# 29-USB_2_0_INTERFACE.net
KiCad netlist of a schematic drawn in Altium Designer
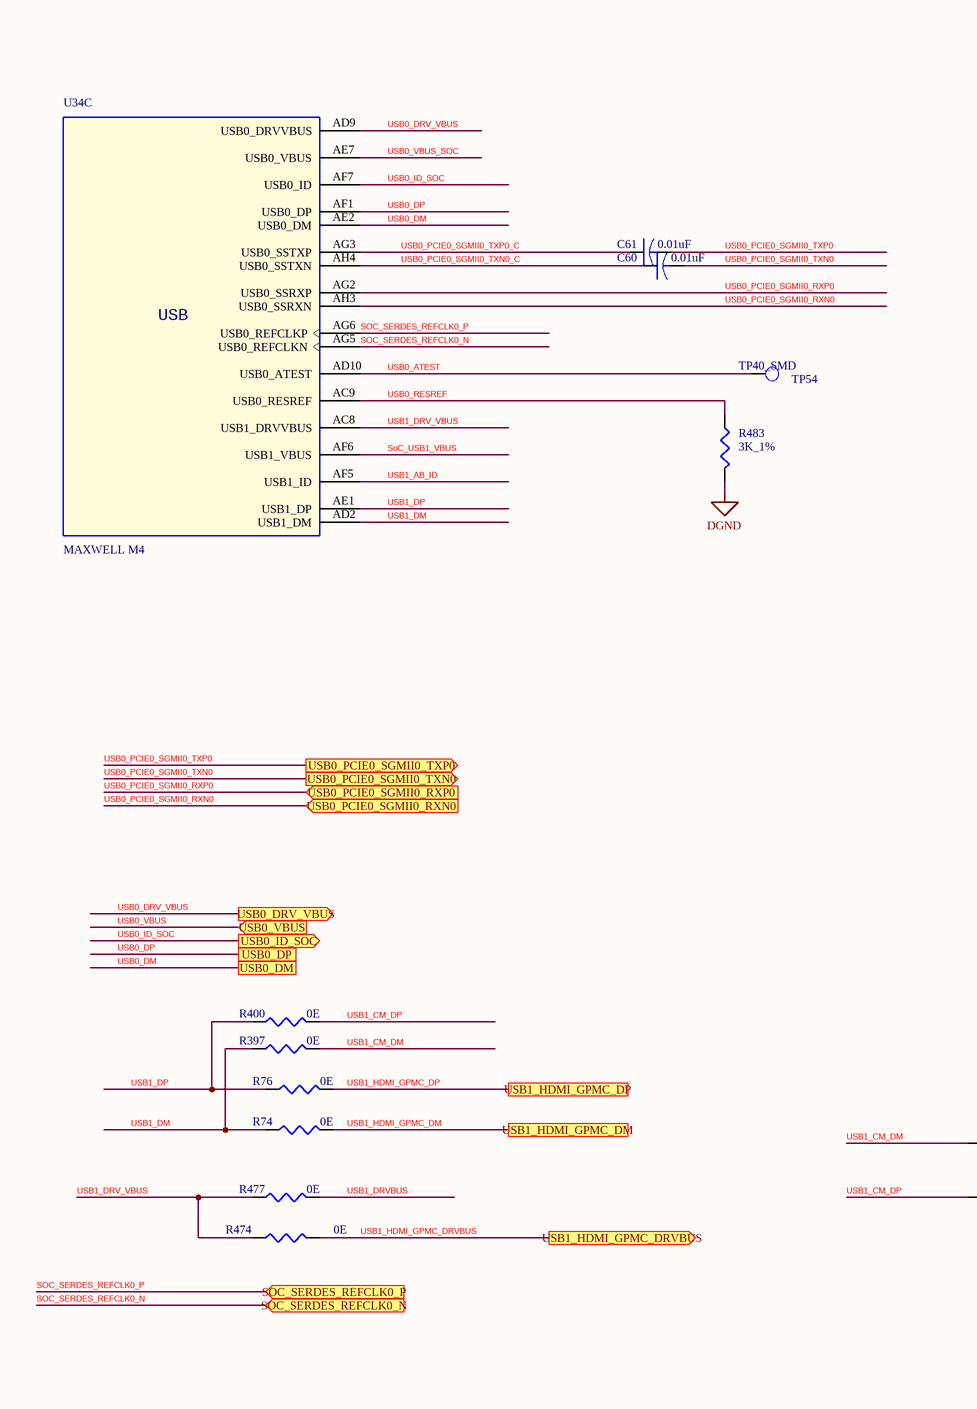
[diagram p0: 29-USB 2.0 INTERFACE.SchDoc, left]
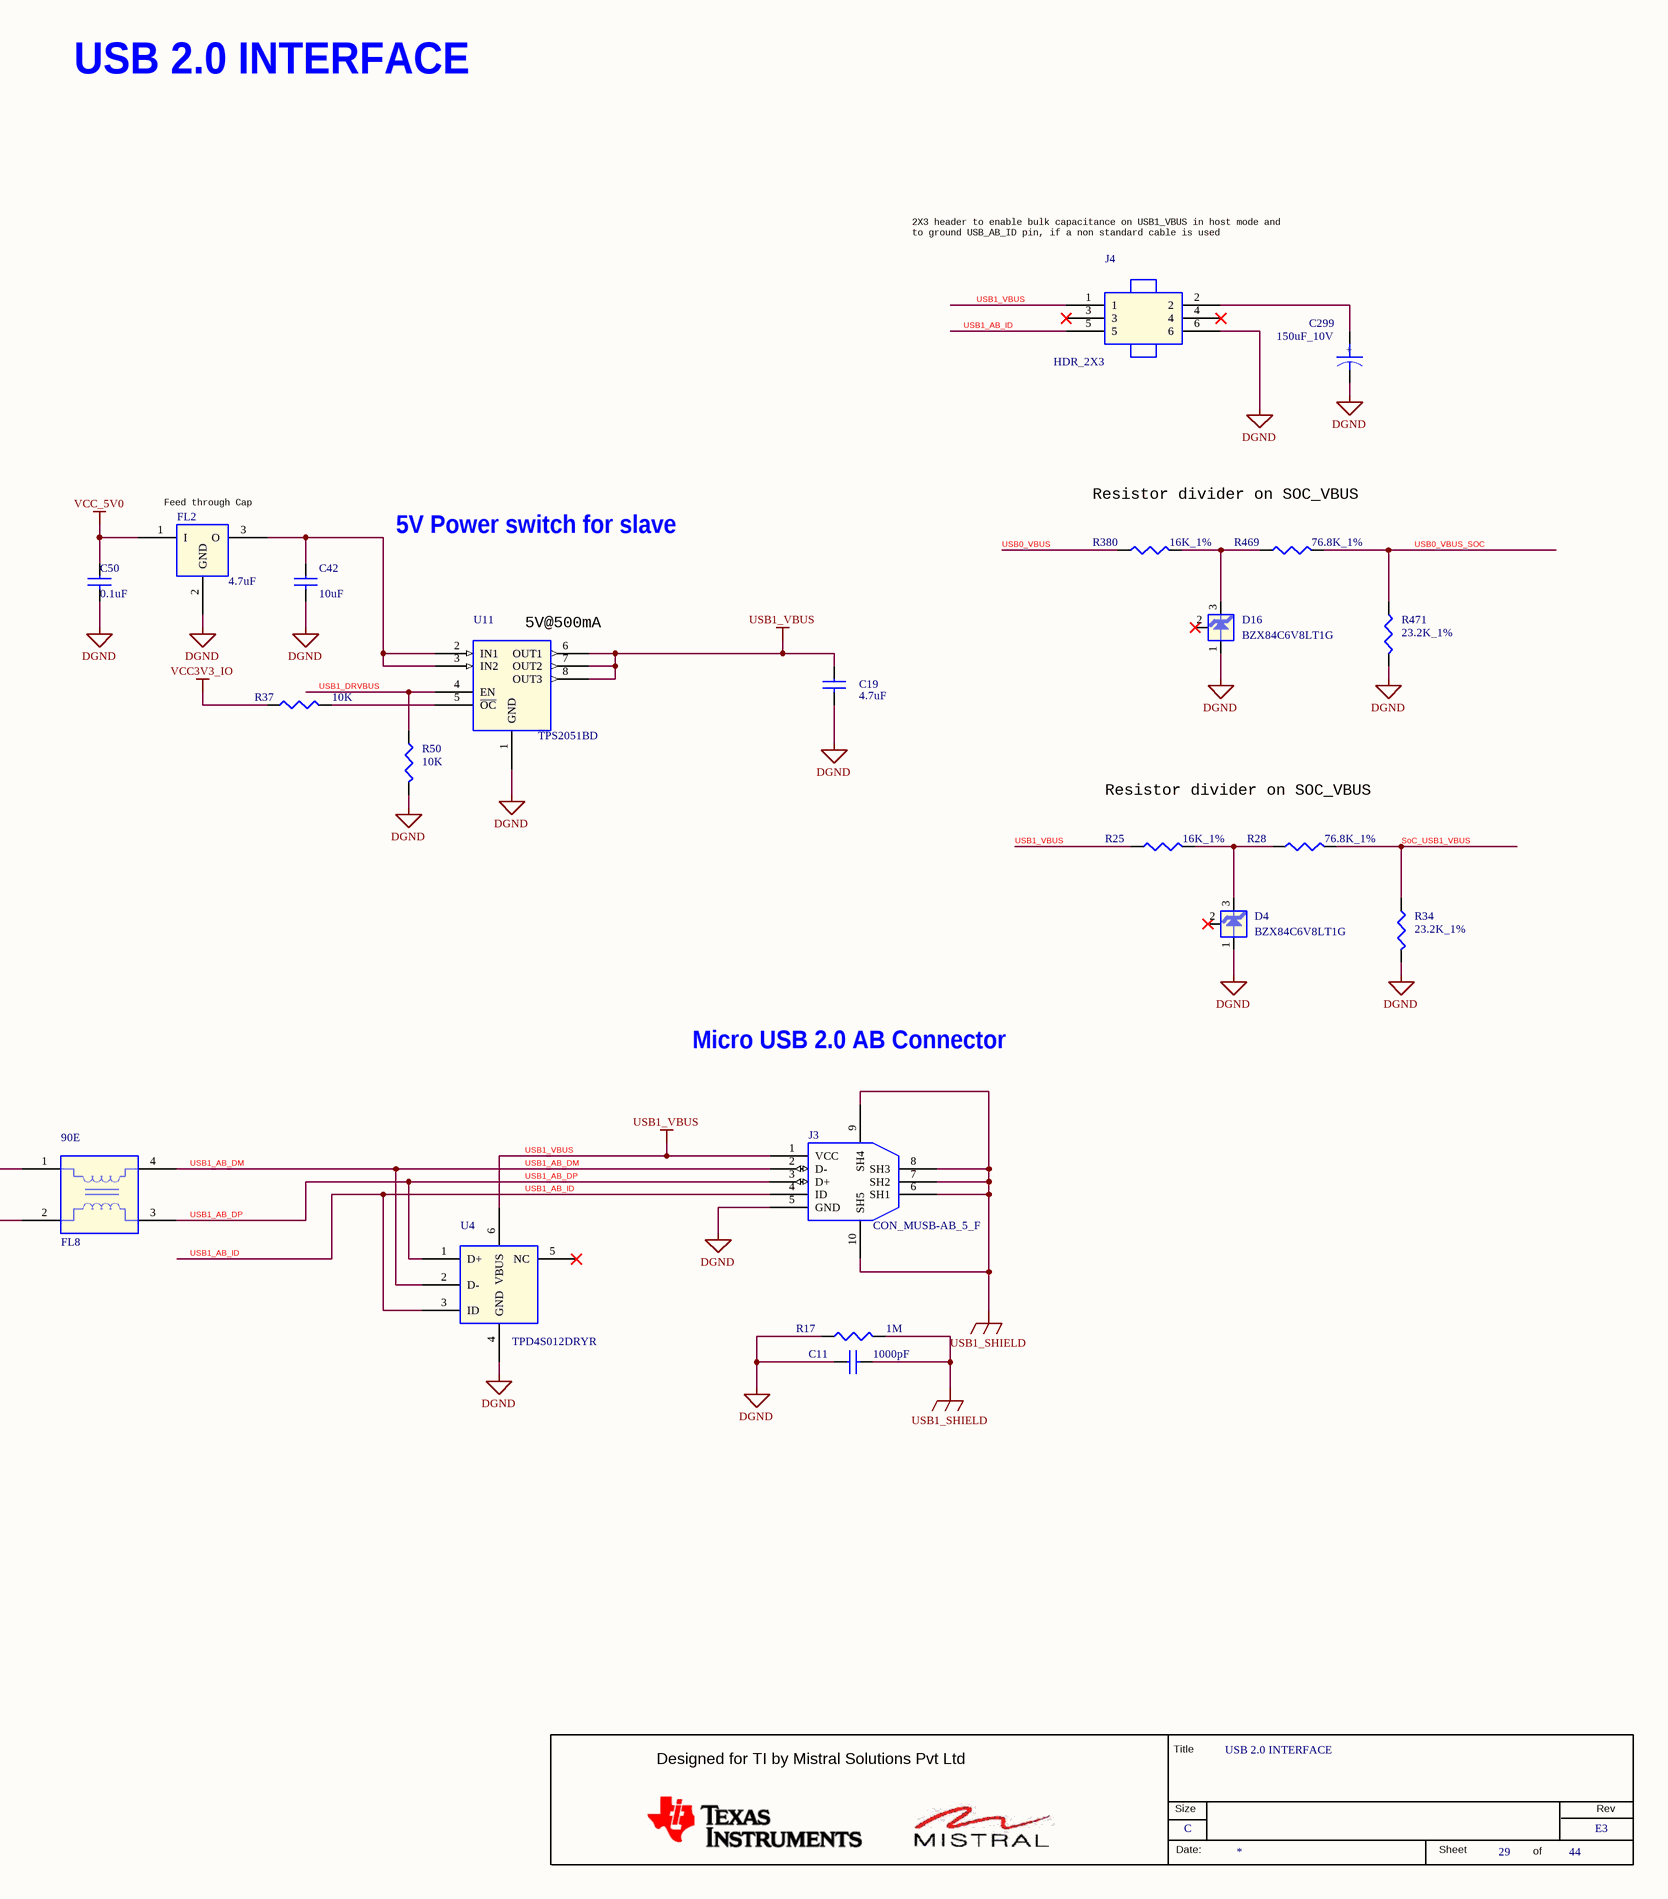
[diagram p1: 29-USB 2.0 INTERFACE.SchDoc, right]

(export (version "E")
  (design (tool "Eeschema 10.0.6"))
  (components
    (comp (ref "C11")
      (value "1000pF")
      (footprint "CAP1206")
      (description "CAP CERAMIC 1000pF 2KV 10% X7R 1206")
      (fields (field (name "DISTRIBUTOR_PART_NUMBER") "478-2956-1-ND") (field (name "VOLTAGE") "2KV"))
      (libsource (lib "*") (part "CAP_Dup5"))
    )
    (comp (ref "C19")
      (value "4.7uF")
      (footprint "CAP0402_0-75")
      (description "CAP CERAMIC 4.7uF 10V 20% X5R 0402")
      (fields
        (field (name "MISTRAL PART NO") "120012060002-R")
        (field (name "MFR_PART_NUMBER") "0402ZD475MAT2A")
      )
      (libsource (lib "*") (part "CAP_Dup5"))
    )
    (comp (ref "C42")
      (value "10uF")
      (footprint "CAP0603_1")
      (description "CAP CERAMIC 10uF 10V 10% X5R 0603")
      (fields (field (name "DISTRIBUTOR_PART_NUMBER") "478-10766-1-ND") (field (name "VOLTAGE") "10V"))
      (libsource (lib "*") (part "CAP_Dup5"))
    )
    (comp (ref "C50")
      (value "0.1uF")
      (footprint "CAP0201_0-5")
      (description "CAP CERAMIC 0.1uF 16V 10% X5R 0201")
      (fields
        (field (name "MISTRAL PART NO") "120009030072-R")
        (field (name "MFR_PART_NUMBER") "GRM033R61C104KE84J")
      )
      (libsource (lib "*") (part "CAP_Dup5"))
    )
    (comp (ref "C60")
      (value "0.01uF")
      (footprint "CAP0402_0-75")
      (description "CAP CERAMIC 0.01uF 10V 10% X7R 0402")
      (fields
        (field (name "MISTRAL PART NO") "120009030017-R")
        (field (name "MFR_PART_NUMBER") "0402ZC103KAT2A")
      )
      (libsource (lib "*") (part "CAP"))
    )
    (comp (ref "C61")
      (value "0.01uF")
      (footprint "CAP0402_0-75")
      (description "CAP CERAMIC 0.01uF 10V 10% X7R 0402")
      (fields (field (name "DISTRIBUTOR_PART_NUMBER") "478-7890-1-ND") (field (name "VOLTAGE") "10V"))
      (libsource (lib "*") (part "CAP"))
    )
    (comp (ref "C299")
      (value "150uF_10V")
      (footprint "CAPT7343D_3-25")
      (description "CAP TANTALUM 150uF 10V 10% ESR 0.9E D7373")
      (fields (field (name "DISTRIBUTOR_PART_NUMBER") "478-11241-1-ND") (field (name "VOLTAGE") "10V"))
      (libsource (lib "*") (part "CAP_POL"))
    )
    (comp (ref "D4")
      (value "BZX84C6V8LT1G")
      (footprint "SOT23-123_1-2")
      (description "DIODE ZENER 250mW 6.8V SOT23-123")
      (fields (field (name "MISTRAL PART NO") "130017100002-R") (field (name "TOLERANCE") "NA"))
      (libsource (lib "*") (part "DIODE_ZENER_SOT23_13"))
    )
    (comp (ref "D16")
      (value "BZX84C6V8LT1G")
      (footprint "SOT23-123_1-2")
      (description "DIODE ZENER 250mW 6.8V SOT23-123")
      (fields (field (name "MISTRAL PART NO") "130017100002-R") (field (name "TOLERANCE") "NA"))
      (libsource (lib "*") (part "DIODE_ZENER_SOT23_13"))
    )
    (comp (ref "FL2")
      (value "4.7uF")
      (footprint "EMIFIL_NFM21P_0805_1")
      (description "PASSIVE FILTER EMI 4.7uF 0805-3")
      (fields (field (name "DISTRIBUTOR_PART_NUMBER") "NA") (field (name "MFR_PART_NUMBER") "NFM21PC475B1A3"))
      (libsource (lib "*") (part "EMI_FILTER"))
    )
    (comp (ref "FL8")
      (value "90E")
      (footprint "IND4_ACM2012_90X50_SMD_1-3")
      (description "PASSIVE FILTER COMMON MODE 90E 400mA SMD")
      (fields
        (field (name "DISTRIBUTOR_PART_NUMBER") "445-2207-1-ND")
        (field (name "MFR_PART_NUMBER") "ACM2012-900-2P-T002")
      )
      (libsource (lib "*") (part "EMIFILTER_ACM"))
    )
    (comp (ref "J3")
      (value "CON_MUSB-AB_5_F")
      (footprint "CON_USBAB5_475900001_S_R_S_3-1")
      (description "CON MICRO USB-AB TYPE 5POS FEMALE RT SMD")
      (fields (field (name "DISTRIBUTOR_PART_NUMBER") "WM17144CT-ND") (field (name "VOLTAGE") "NA"))
      (libsource (lib "*") (part "CON_USB_MINI-AB_10"))
    )
    (comp (ref "J4")
      (value "HDR_2X3")
      (footprint "TMDX654GPEVM_BRD:HDR_2X3_TSW-103-07-D_S_T_8-4")
      (description "CON HDR 2X3 2.54MM PITCH ST TH")
      (fields
        (field (name "MISTRAL PART NO") "150018010019-R")
        (field (name "MFR_PART_NUMBER") "TSW-103-07-T-D")
      )
      (libsource (lib "*") (part "HEADER_3X2"))
    )
    (comp (ref "R17")
      (value "1M")
      (footprint "RES0603_0-75")
      (description "RES 1M 1/10W 5% 0603")
      (fields (field (name "DISTRIBUTOR_PART_NUMBER") "P1.0MGCT-ND") (field (name "VOLTAGE") "NA"))
      (libsource (lib "*") (part "RESISTOR_Dup5"))
    )
    (comp (ref "R25")
      (value "16K_1%")
      (footprint "RES0402")
      (description "RES 16K 1/16W 1% 0402")
      (fields
        (field (name "MISTRAL PART NO") "110011030003-R")
        (field (name "MFR_PART_NUMBER") "MCR01MRTF1602")
      )
      (libsource (lib "*") (part "RESISTOR_Dup5"))
    )
    (comp (ref "R28")
      (value "76.8K_1%")
      (footprint "RES0402")
      (description "RES 76.8K 1/16W 1% 0402")
      (fields (field (name "DISTRIBUTOR_PART_NUMBER") "YAG3230CT-ND") (field (name "VOLTAGE") "NA"))
      (libsource (lib "*") (part "RESISTOR_Dup5"))
    )
    (comp (ref "R34")
      (value "23.2K_1%")
      (footprint "RES0402")
      (description "RES 23.2K 1/16W 1% 0402")
      (fields
        (field (name "MISTRAL PART NO") "110015080017-R")
        (field (name "MFR_PART_NUMBER") "CRCW040223K2FKED")
      )
      (libsource (lib "*") (part "RESISTOR_Dup5"))
    )
    (comp (ref "R37")
      (value "10K")
      (footprint "RES0402_0-5")
      (description "RES 10K 1/16W 5% 0402")
      (fields (field (name "DISTRIBUTOR_PART_NUMBER") "311-10KJRCT-ND") (field (name "VOLTAGE") "NA"))
      (libsource (lib "*") (part "RESISTOR_Dup5"))
    )
    (comp (ref "R50")
      (value "10K")
      (footprint "RES0402_0-5")
      (description "RES 10K 1/16W 5% 0402")
      (fields
        (field (name "MISTRAL PART NO") "110009030208-R")
        (field (name "MFR_PART_NUMBER") "RC0402JR-0710KL")
      )
      (libsource (lib "*") (part "RESISTOR_Dup5"))
    )
    (comp (ref "R74")
      (value "0E")
      (footprint "RES0402_0-5")
      (description "RES 0E 1/16W 0402")
      (fields (field (name "DISTRIBUTOR_PART_NUMBER") "541-0.0JCT-ND") (field (name "VOLTAGE") "NA"))
      (libsource (lib "*") (part "RESISTOR_Dup5"))
    )
    (comp (ref "R76")
      (value "0E")
      (footprint "RES0402_0-5")
      (description "RES 0E 1/16W 0402")
      (fields (field (name "DISTRIBUTOR_PART_NUMBER") "541-0.0JCT-ND") (field (name "VOLTAGE") "NA"))
      (libsource (lib "*") (part "RESISTOR_Dup5"))
    )
    (comp (ref "R380")
      (value "16K_1%")
      (footprint "RES0402")
      (description "RES 16K 1/16W 1% 0402")
      (fields
        (field (name "MISTRAL PART NO") "110011030003-R")
        (field (name "MFR_PART_NUMBER") "MCR01MRTF1602")
      )
      (libsource (lib "*") (part "RESISTOR_Dup5"))
    )
    (comp (ref "R397")
      (value "0E")
      (footprint "RES0402_0-5")
      (description "RES 0E 1/16W 0402")
      (fields (field (name "DISTRIBUTOR_PART_NUMBER") "541-0.0JCT-ND") (field (name "VOLTAGE") "NA"))
      (libsource (lib "*") (part "RESISTOR_Dup4"))
    )
    (comp (ref "R400")
      (value "0E")
      (footprint "RES0402_0-5")
      (description "RES 0E 1/16W 0402")
      (fields (field (name "DISTRIBUTOR_PART_NUMBER") "541-0.0JCT-ND") (field (name "VOLTAGE") "NA"))
      (libsource (lib "*") (part "RESISTOR_Dup4"))
    )
    (comp (ref "R469")
      (value "76.8K_1%")
      (footprint "RES0402")
      (description "RES 76.8K 1/16W 1% 0402")
      (fields (field (name "DISTRIBUTOR_PART_NUMBER") "YAG3230CT-ND") (field (name "VOLTAGE") "NA"))
      (libsource (lib "*") (part "RESISTOR_Dup5"))
    )
    (comp (ref "R471")
      (value "23.2K_1%")
      (footprint "RES0402")
      (description "RES 23.2K 1/16W 1% 0402")
      (fields
        (field (name "MISTRAL PART NO") "110015080017-R")
        (field (name "MFR_PART_NUMBER") "CRCW040223K2FKED")
      )
      (libsource (lib "*") (part "RESISTOR_Dup5"))
    )
    (comp (ref "R474")
      (value "0E")
      (footprint "RES0402_0-5")
      (description "RES 0E 1/16W 0402")
      (fields (field (name "DISTRIBUTOR_PART_NUMBER") "541-0.0JCT-ND") (field (name "VOLTAGE") "NA"))
      (libsource (lib "*") (part "RESISTOR_Dup5"))
    )
    (comp (ref "R477")
      (value "0E")
      (footprint "RES0402_0-5")
      (description "RES 0E 1/16W 0402")
      (fields (field (name "DISTRIBUTOR_PART_NUMBER") "541-0.0JCT-ND") (field (name "VOLTAGE") "NA"))
      (libsource (lib "*") (part "RESISTOR_Dup4"))
    )
    (comp (ref "R483")
      (value "3K_1%")
      (footprint "RES0402_0-5")
      (description "RES 3K 1/16W 1% 0402")
      (fields (field (name "DISTRIBUTOR_PART_NUMBER") "311-3KLRCT-ND") (field (name "VOLTAGE") "NA"))
      (libsource (lib "*") (part "RESISTOR_Dup5"))
    )
    (comp (ref "TP54")
      (value "TP40_SMD")
      (footprint "TP40_SMD")
      (description "TESTPOINT CIR 40 SMD")
      (fields (field (name "DISTRIBUTOR_PART_NUMBER") "NA") (field (name "MISTRAL PART NO") "130009030933"))
      (libsource (lib "*") (part "TESTPOINT"))
    )
    (comp (ref "U4")
      (value "TPD4S012DRYR")
      (footprint "SON6_19-68_40X60_PB_0-6")
      (description "IC 4CH ESD SOLUTION SON6")
      (fields (field (name "DISTRIBUTOR_PART_NUMBER") "296-24244-1-ND") (field (name "VOLTAGE") "NA"))
      (libsource (lib "*") (part "TPD4S012DRY_SON6"))
    )
    (comp (ref "U11")
      (value "TPS2051BD")
      (footprint "SOIC8_1-8")
      (description "IC POWER DISTRIBUTION SWITCH SOIC8")
      (fields
        (field (name "DISTRIBUTOR_PART_NUMBER") "296-26911-5-ND")
        (field (name "VOLTAGE") "NA")
        (field (name "LIBRARY PATH") "Y~{:}MIS_DATABAS~{E}Librar~{y}ALTIUM_TOO~{L}SCHEMATICS_PART~{S}MS_MISCPOWER_Library.schlib")
      )
      (libsource (lib "*") (part "TPS2051BD_SOIC8"))
    )
    (comp (ref "U34")
      (value "MAXWELL M4")
      (footprint "BGA784_31-49_910X910_1-7")
      (description "IC MAXWELL MICRO CONTROLLER UNIT BGA784")
      (fields (field (name "DISTRIBUTOR_PART_NUMBER") "NA") (field (name "MFR_PART_NUMBER") "MAXWELL M4_EVM"))
      (libsource (lib "*") (part "AM654X_BGA784"))
    )
  )
  (nets
    (net (code "1") (name "/SOC_SERDES_REFCLK0_N") (class "Default")
      (node (ref "U34") (pin "AG5") (pinfunction "USB0_REFCLKN_AG5") (pintype "passive"))
    )
    (net (code "2") (name "/SOC_SERDES_REFCLK0_P") (class "Default")
      (node (ref "U34") (pin "AG6") (pinfunction "USB0_REFCLKP_AG6") (pintype "passive"))
    )
    (net (code "3") (name "/SoC_USB1_VBUS") (class "Default")
      (node (ref "R28") (pin "2") (pinfunction "2_2") (pintype "passive"))
      (node (ref "R34") (pin "1") (pinfunction "1_1") (pintype "passive"))
      (node (ref "U34") (pin "AF6") (pinfunction "USB1_VBUS_AF6") (pintype "passive"))
    )
    (net (code "4") (name "/USB0_ATEST") (class "Default")
      (node (ref "TP54") (pin "1") (pinfunction "TP_1") (pintype "passive"))
      (node (ref "U34") (pin "AD10") (pinfunction "USB0_ATEST_AD10") (pintype "passive"))
    )
    (net (code "5") (name "/USB0_DM") (class "Default")
      (node (ref "U34") (pin "AE2") (pinfunction "USB0_DM_AE2") (pintype "passive"))
    )
    (net (code "6") (name "/USB0_DP") (class "Default")
      (node (ref "U34") (pin "AF1") (pinfunction "USB0_DP_AF1") (pintype "passive"))
    )
    (net (code "7") (name "/USB0_DRV_VBUS") (class "Default")
      (node (ref "U34") (pin "AD9") (pinfunction "USB0_DRVVBUS_AD9") (pintype "passive"))
    )
    (net (code "8") (name "/USB0_ID_SOC") (class "Default")
      (node (ref "U34") (pin "AF7") (pinfunction "USB0_ID_AF7") (pintype "passive"))
    )
    (net (code "9") (name "/USB0_PCIE0_SGMII0_RXN0") (class "Default")
      (node (ref "U34") (pin "AH3") (pinfunction "USB0_SSRXN_AH3") (pintype "passive"))
    )
    (net (code "10") (name "/USB0_PCIE0_SGMII0_RXP0") (class "Default")
      (node (ref "U34") (pin "AG2") (pinfunction "USB0_SSRXP_AG2") (pintype "passive"))
    )
    (net (code "11") (name "/USB0_PCIE0_SGMII0_TXN0") (class "Default")
      (node (ref "C60") (pin "2") (pinfunction "2_2") (pintype "passive"))
    )
    (net (code "12") (name "/USB0_PCIE0_SGMII0_TXN0_C") (class "Default")
      (node (ref "C60") (pin "1") (pinfunction "1_1") (pintype "passive"))
      (node (ref "U34") (pin "AH4") (pinfunction "USB0_SSTXN_AH4") (pintype "passive"))
    )
    (net (code "13") (name "/USB0_PCIE0_SGMII0_TXP0") (class "Default")
      (node (ref "C61") (pin "2") (pinfunction "2_2") (pintype "passive"))
    )
    (net (code "14") (name "/USB0_PCIE0_SGMII0_TXP0_C") (class "Default")
      (node (ref "C61") (pin "1") (pinfunction "1_1") (pintype "passive"))
      (node (ref "U34") (pin "AG3") (pinfunction "USB0_SSTXP_AG3") (pintype "passive"))
    )
    (net (code "15") (name "/USB0_RESREF") (class "Default")
      (node (ref "R483") (pin "1") (pinfunction "1_1") (pintype "passive"))
      (node (ref "U34") (pin "AC9") (pinfunction "USB0_RESREF_AC9") (pintype "passive"))
    )
    (net (code "16") (name "/USB0_VBUS") (class "Default")
      (node (ref "R380") (pin "1") (pinfunction "1_1") (pintype "passive"))
    )
    (net (code "17") (name "/USB0_VBUS_SOC") (class "Default")
      (node (ref "R469") (pin "2") (pinfunction "2_2") (pintype "passive"))
      (node (ref "R471") (pin "1") (pinfunction "1_1") (pintype "passive"))
      (node (ref "U34") (pin "AE7") (pinfunction "USB0_VBUS_AE7") (pintype "passive"))
    )
    (net (code "18") (name "/USB1_AB_DM") (class "Default")
      (node (ref "FL8") (pin "4") (pinfunction "4_4") (pintype "passive"))
      (node (ref "J3") (pin "2") (pinfunction "D-_2") (pintype "bidirectional"))
      (node (ref "U4") (pin "2") (pinfunction "D-_2") (pintype "passive"))
    )
    (net (code "19") (name "/USB1_AB_DP") (class "Default")
      (node (ref "FL8") (pin "3") (pinfunction "3_3") (pintype "passive"))
      (node (ref "J3") (pin "3") (pinfunction "D+_3") (pintype "bidirectional"))
      (node (ref "U4") (pin "1") (pinfunction "D+_1") (pintype "passive"))
    )
    (net (code "20") (name "/USB1_AB_ID") (class "Default")
      (node (ref "J3") (pin "4") (pinfunction "ID_4") (pintype "passive"))
      (node (ref "J4") (pin "5") (pinfunction "5_5") (pintype "passive"))
      (node (ref "U34") (pin "AF5") (pinfunction "USB1_ID_AF5") (pintype "passive"))
      (node (ref "U4") (pin "3") (pinfunction "ID_3") (pintype "passive"))
    )
    (net (code "21") (name "/USB1_CM_DM") (class "Default")
      (node (ref "FL8") (pin "1") (pinfunction "1_1") (pintype "passive"))
      (node (ref "R397") (pin "2") (pinfunction "2_2") (pintype "passive"))
    )
    (net (code "22") (name "/USB1_CM_DP") (class "Default")
      (node (ref "FL8") (pin "2") (pinfunction "2_2") (pintype "passive"))
      (node (ref "R400") (pin "2") (pinfunction "2_2") (pintype "passive"))
    )
    (net (code "23") (name "/USB1_DM") (class "Default")
      (node (ref "R397") (pin "1") (pinfunction "1_1") (pintype "passive"))
      (node (ref "R74") (pin "2") (pinfunction "2_2") (pintype "passive"))
      (node (ref "U34") (pin "AD2") (pinfunction "USB1_DM_AD2") (pintype "passive"))
    )
    (net (code "24") (name "/USB1_DP") (class "Default")
      (node (ref "R400") (pin "1") (pinfunction "1_1") (pintype "passive"))
      (node (ref "R76") (pin "2") (pinfunction "2_2") (pintype "passive"))
      (node (ref "U34") (pin "AE1") (pinfunction "USB1_DP_AE1") (pintype "passive"))
    )
    (net (code "25") (name "/USB1_DRVBUS") (class "Default")
      (node (ref "R477") (pin "2") (pinfunction "2_2") (pintype "passive"))
      (node (ref "R50") (pin "1") (pinfunction "1_1") (pintype "passive"))
      (node (ref "U11") (pin "4") (pinfunction "EN_4") (pintype "passive"))
    )
    (net (code "26") (name "/USB1_DRV_VBUS") (class "Default")
      (node (ref "R474") (pin "2") (pinfunction "2_2") (pintype "passive"))
      (node (ref "R477") (pin "1") (pinfunction "1_1") (pintype "passive"))
      (node (ref "U34") (pin "AC8") (pinfunction "USB1_DRVVBUS_AC8") (pintype "passive"))
    )
    (net (code "27") (name "/USB1_HDMI_GPMC_DM") (class "Default")
      (node (ref "R74") (pin "1") (pinfunction "1_1") (pintype "passive"))
    )
    (net (code "28") (name "/USB1_HDMI_GPMC_DP") (class "Default")
      (node (ref "R76") (pin "1") (pinfunction "1_1") (pintype "passive"))
    )
    (net (code "29") (name "/USB1_HDMI_GPMC_DRVBUS") (class "Default")
      (node (ref "R474") (pin "1") (pinfunction "1_1") (pintype "passive"))
    )
    (net (code "30") (name "DGND") (class "Default")
      (node (ref "C11") (pin "1") (pinfunction "1_1") (pintype "passive"))
      (node (ref "C19") (pin "2") (pinfunction "2_2") (pintype "passive"))
      (node (ref "C299") (pin "2") (pinfunction "2_2") (pintype "passive"))
      (node (ref "C42") (pin "2") (pinfunction "2_2") (pintype "passive"))
      (node (ref "C50") (pin "2") (pinfunction "2_2") (pintype "passive"))
      (node (ref "D16") (pin "1") (pinfunction "A_1") (pintype "passive"))
      (node (ref "D4") (pin "1") (pinfunction "A_1") (pintype "passive"))
      (node (ref "FL2") (pin "2") (pinfunction "GND_2") (pintype "power_in"))
      (node (ref "J3") (pin "5") (pinfunction "GND_5") (pintype "power_in"))
      (node (ref "J4") (pin "6") (pinfunction "6_6") (pintype "passive"))
      (node (ref "R17") (pin "1") (pinfunction "1_1") (pintype "passive"))
      (node (ref "R34") (pin "2") (pinfunction "2_2") (pintype "passive"))
      (node (ref "R471") (pin "2") (pinfunction "2_2") (pintype "passive"))
      (node (ref "R483") (pin "2") (pinfunction "2_2") (pintype "passive"))
      (node (ref "R50") (pin "2") (pinfunction "2_2") (pintype "passive"))
      (node (ref "U11") (pin "1") (pinfunction "GND_1") (pintype "power_in"))
      (node (ref "U4") (pin "4") (pinfunction "GND_4") (pintype "power_in"))
    )
    (net (code "31") (name "Net-(C299-Pad1)") (class "Default")
      (node (ref "C299") (pin "1") (pinfunction "1_1") (pintype "passive"))
      (node (ref "J4") (pin "2") (pinfunction "2_2") (pintype "passive"))
    )
    (net (code "32") (name "Net-(D4-C)") (class "Default")
      (node (ref "D4") (pin "3") (pinfunction "C_3") (pintype "passive"))
      (node (ref "R25") (pin "2") (pinfunction "2_2") (pintype "passive"))
      (node (ref "R28") (pin "1") (pinfunction "1_1") (pintype "passive"))
    )
    (net (code "33") (name "Net-(D16-C)") (class "Default")
      (node (ref "D16") (pin "3") (pinfunction "C_3") (pintype "passive"))
      (node (ref "R380") (pin "2") (pinfunction "2_2") (pintype "passive"))
      (node (ref "R469") (pin "1") (pinfunction "1_1") (pintype "passive"))
    )
    (net (code "34") (name "Net-(FL2-O)") (class "Default")
      (node (ref "C42") (pin "1") (pinfunction "1_1") (pintype "passive"))
      (node (ref "FL2") (pin "3") (pinfunction "O_3") (pintype "passive"))
      (node (ref "U11") (pin "2") (pinfunction "IN1_2") (pintype "input"))
      (node (ref "U11") (pin "3") (pinfunction "IN2_3") (pintype "input"))
    )
    (net (code "35") (name "Net-(U11-~{OC})") (class "Default")
      (node (ref "R37") (pin "2") (pinfunction "2_2") (pintype "passive"))
      (node (ref "U11") (pin "5") (pinfunction "~{OC}_5") (pintype "passive"))
    )
    (net (code "36") (name "USB1_SHIELD") (class "Default")
      (node (ref "C11") (pin "2") (pinfunction "2_2") (pintype "passive"))
      (node (ref "J3") (pin "10") (pinfunction "SH5_10") (pintype "power_in"))
      (node (ref "J3") (pin "6") (pinfunction "SH1_6") (pintype "power_in"))
      (node (ref "J3") (pin "7") (pinfunction "SH2_7") (pintype "power_in"))
      (node (ref "J3") (pin "8") (pinfunction "SH3_8") (pintype "power_in"))
      (node (ref "J3") (pin "9") (pinfunction "SH4_9") (pintype "power_in"))
      (node (ref "R17") (pin "2") (pinfunction "2_2") (pintype "passive"))
    )
    (net (code "37") (name "USB1_VBUS") (class "Default")
      (node (ref "C19") (pin "1") (pinfunction "1_1") (pintype "passive"))
      (node (ref "J3") (pin "1") (pinfunction "VCC_1") (pintype "power_in"))
      (node (ref "J4") (pin "1") (pinfunction "1_1") (pintype "passive"))
      (node (ref "R25") (pin "1") (pinfunction "1_1") (pintype "passive"))
      (node (ref "U11") (pin "6") (pinfunction "OUT1_6") (pintype "output"))
      (node (ref "U11") (pin "7") (pinfunction "OUT2_7") (pintype "output"))
      (node (ref "U11") (pin "8") (pinfunction "OUT3_8") (pintype "output"))
      (node (ref "U4") (pin "6") (pinfunction "VBUS_6") (pintype "power_in"))
    )
    (net (code "38") (name "VCC3V3_IO") (class "Default")
      (node (ref "R37") (pin "1") (pinfunction "1_1") (pintype "passive"))
    )
    (net (code "39") (name "VCC_5V0") (class "Default")
      (node (ref "C50") (pin "1") (pinfunction "1_1") (pintype "passive"))
      (node (ref "FL2") (pin "1") (pinfunction "I_1") (pintype "passive"))
    )
    (net (code "40") (name "unconnected-(D4-NC-Pad2)") (class "Default")
      (node (ref "D4") (pin "2") (pinfunction "NC_2") (pintype "passive+no_connect"))
    )
    (net (code "41") (name "unconnected-(D16-NC-Pad2)") (class "Default")
      (node (ref "D16") (pin "2") (pinfunction "NC_2") (pintype "passive+no_connect"))
    )
    (net (code "42") (name "unconnected-(J4-Pad3)") (class "Default")
      (node (ref "J4") (pin "3") (pinfunction "3_3") (pintype "passive+no_connect"))
    )
    (net (code "43") (name "unconnected-(J4-Pad4)") (class "Default")
      (node (ref "J4") (pin "4") (pinfunction "4_4") (pintype "passive+no_connect"))
    )
    (net (code "44") (name "unconnected-(U4-NC-Pad5)") (class "Default")
      (node (ref "U4") (pin "5") (pinfunction "NC_5") (pintype "passive+no_connect"))
    )
  )
)
